# aq_mx_v1-5-0a.net
KiCad netlist of a schematic drawn in EAGLE
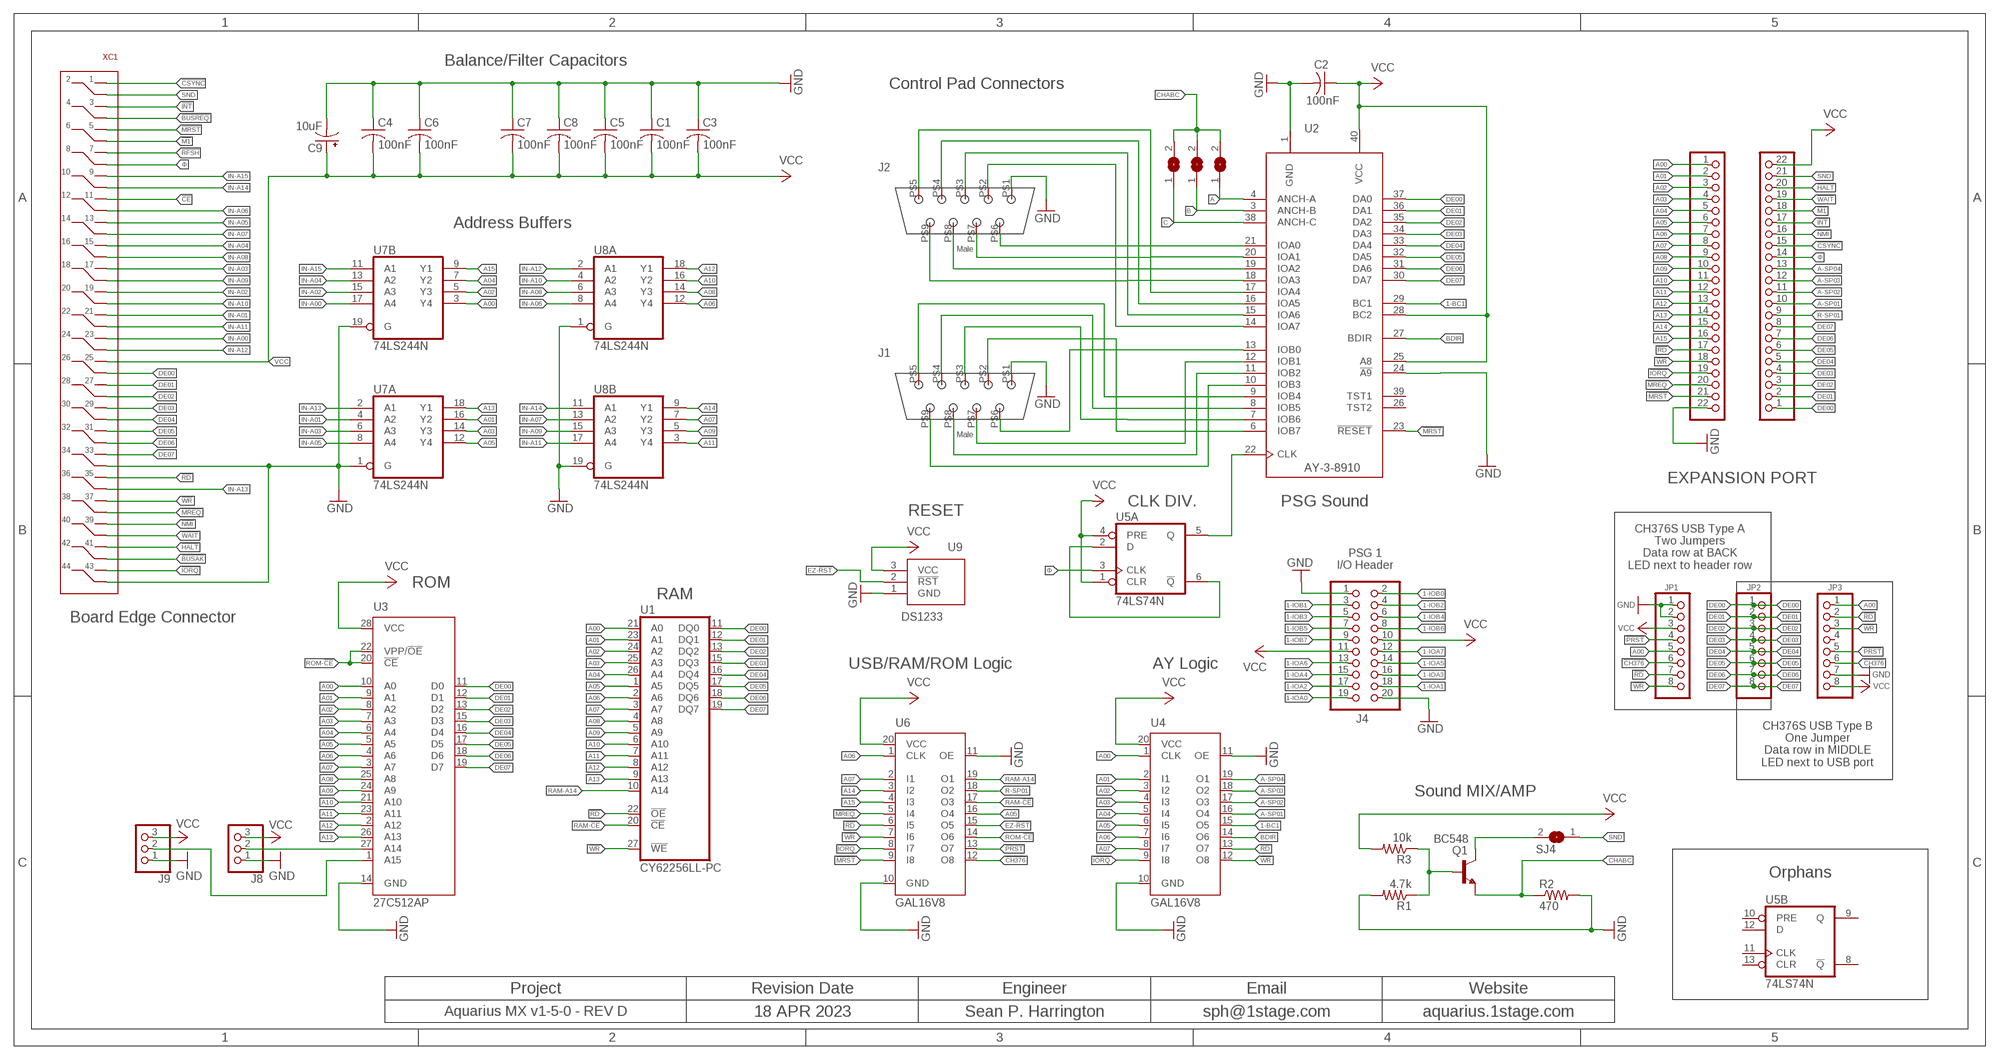
[diagram p0: schematic, sheet 1]

(export (version "E")
  (design (tool "Eeschema 10.0.6"))
  (components
    (comp (ref "C1")
      (value "100nF")
      (footprint "eagle-import:C050-025X075")
      (libsource (lib "eagle-import") (part "C-US050-025X075"))
    )
    (comp (ref "C2")
      (value "100nF")
      (footprint "eagle-import:C050-025X075")
      (libsource (lib "eagle-import") (part "C-US050-025X075"))
    )
    (comp (ref "C3")
      (value "100nF")
      (footprint "eagle-import:C050-025X075")
      (libsource (lib "eagle-import") (part "C-US050-025X075"))
    )
    (comp (ref "C4")
      (value "100nF")
      (footprint "eagle-import:C050-025X075")
      (libsource (lib "eagle-import") (part "C-US050-025X075"))
    )
    (comp (ref "C5")
      (value "100nF")
      (footprint "eagle-import:C050-025X075")
      (libsource (lib "eagle-import") (part "C-US050-025X075"))
    )
    (comp (ref "C6")
      (value "100nF")
      (footprint "eagle-import:C050-025X075")
      (libsource (lib "eagle-import") (part "C-US050-025X075"))
    )
    (comp (ref "C7")
      (value "100nF")
      (footprint "eagle-import:C050-025X075")
      (libsource (lib "eagle-import") (part "C-US050-025X075"))
    )
    (comp (ref "C8")
      (value "100nF")
      (footprint "eagle-import:C050-025X075")
      (libsource (lib "eagle-import") (part "C-US050-025X075"))
    )
    (comp (ref "C9")
      (value "10uF")
      (footprint "eagle-import:E22-6")
      (libsource (lib "eagle-import") (part "CPOL-USE22-6AXIAL"))
    )
    (comp (ref "J1")
      (value "DB9-MALE-RA")
      (footprint "eagle-import:DB9-MALE-RA")
      (libsource (lib "eagle-import") (part "DB9-MALE-RA"))
    )
    (comp (ref "J2")
      (value "DB9-MALE-RA")
      (footprint "eagle-import:DB9-MALE-RA")
      (libsource (lib "eagle-import") (part "DB9-MALE-RA"))
    )
    (comp (ref "J4")
      (value "PINHD-2X10")
      (footprint "eagle-import:2X10")
      (libsource (lib "eagle-import") (part "PINHD-2X10"))
    )
    (comp (ref "J6")
      (value "PINHD-1X22")
      (footprint "eagle-import:1X22")
      (libsource (lib "eagle-import") (part "PINHD-1X22"))
    )
    (comp (ref "J7")
      (value "PINHD-1X22")
      (footprint "eagle-import:1X22")
      (libsource (lib "eagle-import") (part "PINHD-1X22"))
    )
    (comp (ref "J8")
      (value "PINHD-1X3")
      (footprint "eagle-import:1X03")
      (libsource (lib "eagle-import") (part "PINHD-1X3"))
    )
    (comp (ref "J9")
      (value "PINHD-1X3")
      (footprint "eagle-import:1X03")
      (libsource (lib "eagle-import") (part "PINHD-1X3"))
    )
    (comp (ref "JP1")
      (value "PINHD-1X8")
      (footprint "eagle-import:1X08")
      (libsource (lib "eagle-import") (part "PINHD-1X8"))
    )
    (comp (ref "JP2")
      (value "PINHD-1X8")
      (footprint "eagle-import:1X08")
      (libsource (lib "eagle-import") (part "PINHD-1X8"))
    )
    (comp (ref "JP3")
      (value "PINHD-1X8")
      (footprint "eagle-import:1X08")
      (libsource (lib "eagle-import") (part "PINHD-1X8"))
    )
    (comp (ref "Q1")
      (value "BC548")
      (footprint "eagle-import:TO92-CBE")
      (libsource (lib "eagle-import") (part "-NPN-TO92-CBEBC548"))
    )
    (comp (ref "R1")
      (value "4.7k")
      (footprint "eagle-import:0204_7")
      (libsource (lib "eagle-import") (part "R-US_0204/7"))
    )
    (comp (ref "R2")
      (value "470")
      (footprint "eagle-import:0204_7")
      (libsource (lib "eagle-import") (part "R-US_0204/7"))
    )
    (comp (ref "R3")
      (value "10k")
      (footprint "eagle-import:0204_7")
      (libsource (lib "eagle-import") (part "R-US_0204/7"))
    )
    (comp (ref "SJ1") (value "SJ") (footprint "eagle-import:SJ") (libsource (lib "eagle-import") (part "SJ")))
    (comp (ref "SJ2") (value "SJ") (footprint "eagle-import:SJ") (libsource (lib "eagle-import") (part "SJ")))
    (comp (ref "SJ3") (value "SJ") (footprint "eagle-import:SJ") (libsource (lib "eagle-import") (part "SJ")))
    (comp (ref "SJ4") (value "SJ") (footprint "eagle-import:SJ") (libsource (lib "eagle-import") (part "SJ")))
    (comp (ref "U1")
      (value "CY62256LL-PC")
      (footprint "eagle-import:DIL28-6")
      (libsource (lib "eagle-import") (part "CY62256LL-?PC"))
    )
    (comp (ref "U2")
      (value "AY-3-8910")
      (footprint "eagle-import:RAD38910-DIL40-6")
      (libsource (lib "eagle-import") (part "RAD38910DIL40-6"))
    )
    (comp (ref "U3")
      (value "27C512AP")
      (footprint "eagle-import:DIL28-6")
      (fields (field (name "MPN") "M27C512-90B6"))
      (libsource (lib "eagle-import") (part "27512APC"))
    )
    (comp (ref "U4")
      (value "GAL16V8")
      (footprint "eagle-import:DIL20")
      (fields (field (name "MPN") "ATF16V8CZ-15PU"))
      (libsource (lib "eagle-import") (part "ATF16V8BP3"))
    )
    (comp (ref "U5")
      (value "74LS74N")
      (footprint "eagle-import:DIL14")
      (libsource (lib "eagle-import") (part "7474NLS"))
    )
    (comp (ref "U6")
      (value "GAL16V8")
      (footprint "eagle-import:DIL20")
      (fields (field (name "MPN") "ATF16V8CZ-15PU"))
      (libsource (lib "eagle-import") (part "ATF16V8BP3"))
    )
    (comp (ref "U7")
      (value "74LS244N")
      (footprint "eagle-import:DIL20")
      (libsource (lib "eagle-import") (part "74244NLS"))
    )
    (comp (ref "U8")
      (value "74LS244N")
      (footprint "eagle-import:DIL20")
      (libsource (lib "eagle-import") (part "74244NLS"))
    )
    (comp (ref "U9")
      (value "DS1233")
      (footprint "eagle-import:TO-92")
      (fields
        (field (name "ARROW_PART_NUMBER") "DS1233-10+")
        (field (name "MOUSER_PART_NUMBER") "700-DS1233-10")
      )
      (libsource (lib "eagle-import") (part "DS1233-10+"))
    )
    (comp (ref "XC1")
      (value "AQ-CART-EDGE")
      (footprint "eagle-import:AQ-CART-EDGE")
      (libsource (lib "eagle-import") (part "AQ-CART-EDGE"))
    )
  )
  (nets
    (net (code "1") (name "/EZ-~{RST}") (class "Default")
      (node (ref "U6") (pin "15") (pinfunction "O5_15") (pintype "output"))
      (node (ref "U9") (pin "2") (pinfunction "~{RST}_2") (pintype "input"))
    )
    (net (code "2") (name "/RAM-~{CE}") (class "Default")
      (node (ref "U1") (pin "20") (pinfunction "~{CE}_20") (pintype "input"))
      (node (ref "U6") (pin "17") (pinfunction "O3_17") (pintype "output"))
    )
    (net (code "3") (name "/ROM-~{CE}") (class "Default")
      (node (ref "U3") (pin "20") (pinfunction "~{CE}_20") (pintype "input"))
      (node (ref "U3") (pin "22") (pinfunction "VPP/~{OE}_22") (pintype "input"))
      (node (ref "U6") (pin "14") (pinfunction "O6_14") (pintype "output"))
    )
    (net (code "4") (name "/~{BUSAK}") (class "Default")
      (node (ref "XC1") (pin "P$42") (pinfunction "X42_P$42") (pintype "bidirectional"))
    )
    (net (code "5") (name "/~{BUSREQ}") (class "Default")
      (node (ref "XC1") (pin "P$4") (pinfunction "X4_P$4") (pintype "bidirectional"))
    )
    (net (code "6") (name "/~{CE}") (class "Default")
      (node (ref "XC1") (pin "P$11") (pinfunction "X11_P$11") (pintype "bidirectional"))
    )
    (net (code "7") (name "/~{CH376}") (class "Default")
      (node (ref "JP1") (pin "6") (pinfunction "6_6") (pintype "passive"))
      (node (ref "JP3") (pin "6") (pinfunction "6_6") (pintype "passive"))
      (node (ref "U6") (pin "12") (pinfunction "O8_12") (pintype "output"))
    )
    (net (code "8") (name "/~{CSYNC}") (class "Default")
      (node (ref "J6") (pin "15") (pinfunction "15_15") (pintype "passive"))
      (node (ref "XC1") (pin "P$1") (pinfunction "X1_P$1") (pintype "bidirectional"))
    )
    (net (code "9") (name "/~{HALT}") (class "Default")
      (node (ref "J6") (pin "20") (pinfunction "20_20") (pintype "passive"))
      (node (ref "XC1") (pin "P$41") (pinfunction "X41_P$41") (pintype "bidirectional"))
    )
    (net (code "10") (name "/~{INT}") (class "Default")
      (node (ref "J6") (pin "17") (pinfunction "17_17") (pintype "passive"))
      (node (ref "XC1") (pin "P$3") (pinfunction "X3_P$3") (pintype "bidirectional"))
    )
    (net (code "11") (name "/~{IORQ}") (class "Default")
      (node (ref "J7") (pin "19") (pinfunction "19_19") (pintype "passive"))
      (node (ref "U4") (pin "9") (pinfunction "I8_9") (pintype "input"))
      (node (ref "U6") (pin "8") (pinfunction "I7_8") (pintype "input"))
      (node (ref "XC1") (pin "P$43") (pinfunction "X43_P$43") (pintype "bidirectional"))
    )
    (net (code "12") (name "/~{M1}") (class "Default")
      (node (ref "J6") (pin "18") (pinfunction "18_18") (pintype "passive"))
      (node (ref "XC1") (pin "P$6") (pinfunction "X6_P$6") (pintype "bidirectional"))
    )
    (net (code "13") (name "/~{MREQ}") (class "Default")
      (node (ref "J7") (pin "20") (pinfunction "20_20") (pintype "passive"))
      (node (ref "U6") (pin "5") (pinfunction "I4_5") (pintype "input"))
      (node (ref "XC1") (pin "P$38") (pinfunction "X38_P$38") (pintype "bidirectional"))
    )
    (net (code "14") (name "/~{MRST}") (class "Default")
      (node (ref "J7") (pin "21") (pinfunction "21_21") (pintype "passive"))
      (node (ref "U2") (pin "23") (pinfunction "~{RESET}_23") (pintype "bidirectional"))
      (node (ref "U6") (pin "9") (pinfunction "I8_9") (pintype "input"))
      (node (ref "XC1") (pin "P$5") (pinfunction "X5_P$5") (pintype "bidirectional"))
    )
    (net (code "15") (name "/~{NMI}") (class "Default")
      (node (ref "J6") (pin "16") (pinfunction "16_16") (pintype "passive"))
      (node (ref "XC1") (pin "P$39") (pinfunction "X39_P$39") (pintype "bidirectional"))
    )
    (net (code "16") (name "/~{PRST}") (class "Default")
      (node (ref "JP1") (pin "4") (pinfunction "4_4") (pintype "passive"))
      (node (ref "JP3") (pin "5") (pinfunction "5_5") (pintype "passive"))
      (node (ref "U6") (pin "13") (pinfunction "O7_13") (pintype "output"))
    )
    (net (code "17") (name "/~{RD}") (class "Default")
      (node (ref "J7") (pin "17") (pinfunction "17_17") (pintype "passive"))
      (node (ref "JP1") (pin "7") (pinfunction "7_7") (pintype "passive"))
      (node (ref "JP3") (pin "2") (pinfunction "2_2") (pintype "passive"))
      (node (ref "U1") (pin "22") (pinfunction "~{OE}_22") (pintype "input"))
      (node (ref "U4") (pin "13") (pinfunction "O7_13") (pintype "output"))
      (node (ref "U6") (pin "6") (pinfunction "I5_6") (pintype "input"))
      (node (ref "XC1") (pin "P$35") (pinfunction "X35_P$35") (pintype "bidirectional"))
    )
    (net (code "18") (name "/~{RFSH}") (class "Default")
      (node (ref "XC1") (pin "P$7") (pinfunction "X7_P$7") (pintype "bidirectional"))
    )
    (net (code "19") (name "/~{WAIT}") (class "Default")
      (node (ref "J6") (pin "19") (pinfunction "19_19") (pintype "passive"))
      (node (ref "XC1") (pin "P$40") (pinfunction "X40_P$40") (pintype "bidirectional"))
    )
    (net (code "20") (name "/~{WR}") (class "Default")
      (node (ref "J7") (pin "18") (pinfunction "18_18") (pintype "passive"))
      (node (ref "JP1") (pin "8") (pinfunction "8_8") (pintype "passive"))
      (node (ref "JP3") (pin "3") (pinfunction "3_3") (pintype "passive"))
      (node (ref "U1") (pin "27") (pinfunction "~{WE}_27") (pintype "input"))
      (node (ref "U4") (pin "12") (pinfunction "O8_12") (pintype "output"))
      (node (ref "U6") (pin "7") (pinfunction "I6_7") (pintype "input"))
      (node (ref "XC1") (pin "P$37") (pinfunction "X37_P$37") (pintype "bidirectional"))
    )
    (net (code "21") (name "1-BC1") (class "Default")
      (node (ref "U2") (pin "29") (pinfunction "BC1_29") (pintype "bidirectional"))
      (node (ref "U4") (pin "15") (pinfunction "O5_15") (pintype "output"))
    )
    (net (code "22") (name "1-IOA0") (class "Default")
      (node (ref "J2") (pin "P$6") (pinfunction "P$6_P$6") (pintype "bidirectional"))
      (node (ref "J4") (pin "19") (pinfunction "19_19") (pintype "passive"))
      (node (ref "U2") (pin "21") (pinfunction "IOA0_21") (pintype "bidirectional"))
    )
    (net (code "23") (name "1-IOA1") (class "Default")
      (node (ref "J2") (pin "P$7") (pinfunction "P$7_P$7") (pintype "bidirectional"))
      (node (ref "J4") (pin "18") (pinfunction "18_18") (pintype "passive"))
      (node (ref "U2") (pin "20") (pinfunction "IOA1_20") (pintype "bidirectional"))
    )
    (net (code "24") (name "1-IOA2") (class "Default")
      (node (ref "J2") (pin "P$8") (pinfunction "P$8_P$8") (pintype "bidirectional"))
      (node (ref "J4") (pin "17") (pinfunction "17_17") (pintype "passive"))
      (node (ref "U2") (pin "19") (pinfunction "IOA2_19") (pintype "bidirectional"))
    )
    (net (code "25") (name "1-IOA3") (class "Default")
      (node (ref "J2") (pin "P$9") (pinfunction "P$9_P$9") (pintype "bidirectional"))
      (node (ref "J4") (pin "16") (pinfunction "16_16") (pintype "passive"))
      (node (ref "U2") (pin "18") (pinfunction "IOA3_18") (pintype "bidirectional"))
    )
    (net (code "26") (name "1-IOA4") (class "Default")
      (node (ref "J2") (pin "P$5") (pinfunction "P$5_P$5") (pintype "bidirectional"))
      (node (ref "J4") (pin "15") (pinfunction "15_15") (pintype "passive"))
      (node (ref "U2") (pin "17") (pinfunction "IOA4_17") (pintype "bidirectional"))
    )
    (net (code "27") (name "1-IOA5") (class "Default")
      (node (ref "J2") (pin "P$4") (pinfunction "P$4_P$4") (pintype "bidirectional"))
      (node (ref "J4") (pin "14") (pinfunction "14_14") (pintype "passive"))
      (node (ref "U2") (pin "16") (pinfunction "IOA5_16") (pintype "bidirectional"))
    )
    (net (code "28") (name "1-IOA6") (class "Default")
      (node (ref "J2") (pin "P$3") (pinfunction "P$3_P$3") (pintype "bidirectional"))
      (node (ref "J4") (pin "13") (pinfunction "13_13") (pintype "passive"))
      (node (ref "U2") (pin "15") (pinfunction "IOA6_15") (pintype "bidirectional"))
    )
    (net (code "29") (name "1-IOA7") (class "Default")
      (node (ref "J2") (pin "P$2") (pinfunction "P$2_P$2") (pintype "bidirectional"))
      (node (ref "J4") (pin "12") (pinfunction "12_12") (pintype "passive"))
      (node (ref "U2") (pin "14") (pinfunction "IOA7_14") (pintype "bidirectional"))
    )
    (net (code "30") (name "1-IOB0") (class "Default")
      (node (ref "J1") (pin "P$6") (pinfunction "P$6_P$6") (pintype "bidirectional"))
      (node (ref "J4") (pin "2") (pinfunction "2_2") (pintype "passive"))
      (node (ref "U2") (pin "13") (pinfunction "IOB0_13") (pintype "bidirectional"))
    )
    (net (code "31") (name "1-IOB1") (class "Default")
      (node (ref "J1") (pin "P$7") (pinfunction "P$7_P$7") (pintype "bidirectional"))
      (node (ref "J4") (pin "3") (pinfunction "3_3") (pintype "passive"))
      (node (ref "U2") (pin "12") (pinfunction "IOB1_12") (pintype "bidirectional"))
    )
    (net (code "32") (name "1-IOB2") (class "Default")
      (node (ref "J1") (pin "P$8") (pinfunction "P$8_P$8") (pintype "bidirectional"))
      (node (ref "J4") (pin "4") (pinfunction "4_4") (pintype "passive"))
      (node (ref "U2") (pin "11") (pinfunction "IOB2_11") (pintype "bidirectional"))
    )
    (net (code "33") (name "1-IOB3") (class "Default")
      (node (ref "J1") (pin "P$9") (pinfunction "P$9_P$9") (pintype "bidirectional"))
      (node (ref "J4") (pin "5") (pinfunction "5_5") (pintype "passive"))
      (node (ref "U2") (pin "10") (pinfunction "IOB3_10") (pintype "bidirectional"))
    )
    (net (code "34") (name "1-IOB4") (class "Default")
      (node (ref "J1") (pin "P$5") (pinfunction "P$5_P$5") (pintype "bidirectional"))
      (node (ref "J4") (pin "6") (pinfunction "6_6") (pintype "passive"))
      (node (ref "U2") (pin "9") (pinfunction "IOB4_9") (pintype "bidirectional"))
    )
    (net (code "35") (name "1-IOB5") (class "Default")
      (node (ref "J1") (pin "P$4") (pinfunction "P$4_P$4") (pintype "bidirectional"))
      (node (ref "J4") (pin "7") (pinfunction "7_7") (pintype "passive"))
      (node (ref "U2") (pin "8") (pinfunction "IOB5_8") (pintype "bidirectional"))
    )
    (net (code "36") (name "1-IOB6") (class "Default")
      (node (ref "J1") (pin "P$3") (pinfunction "P$3_P$3") (pintype "bidirectional"))
      (node (ref "J4") (pin "8") (pinfunction "8_8") (pintype "passive"))
      (node (ref "U2") (pin "7") (pinfunction "IOB6_7") (pintype "bidirectional"))
    )
    (net (code "37") (name "1-IOB7") (class "Default")
      (node (ref "J1") (pin "P$2") (pinfunction "P$2_P$2") (pintype "bidirectional"))
      (node (ref "J4") (pin "9") (pinfunction "9_9") (pintype "passive"))
      (node (ref "U2") (pin "6") (pinfunction "IOB7_6") (pintype "bidirectional"))
    )
    (net (code "38") (name "A") (class "Default")
      (node (ref "SJ1") (pin "1") (pinfunction "1_1") (pintype "passive"))
      (node (ref "U2") (pin "4") (pinfunction "ANCH-A_4") (pintype "bidirectional"))
    )
    (net (code "39") (name "A-SP01") (class "Default")
      (node (ref "J6") (pin "10") (pinfunction "10_10") (pintype "passive"))
      (node (ref "U4") (pin "16") (pinfunction "O4_16") (pintype "output"))
    )
    (net (code "40") (name "A-SP02") (class "Default")
      (node (ref "J6") (pin "11") (pinfunction "11_11") (pintype "passive"))
      (node (ref "U4") (pin "17") (pinfunction "O3_17") (pintype "output"))
    )
    (net (code "41") (name "A-SP03") (class "Default")
      (node (ref "J6") (pin "12") (pinfunction "12_12") (pintype "passive"))
      (node (ref "U4") (pin "18") (pinfunction "O2_18") (pintype "output"))
    )
    (net (code "42") (name "A-SP04") (class "Default")
      (node (ref "J6") (pin "13") (pinfunction "13_13") (pintype "passive"))
      (node (ref "U4") (pin "19") (pinfunction "O1_19") (pintype "output"))
    )
    (net (code "43") (name "A00") (class "Default")
      (node (ref "J7") (pin "1") (pinfunction "1_1") (pintype "passive"))
      (node (ref "JP1") (pin "5") (pinfunction "5_5") (pintype "passive"))
      (node (ref "JP3") (pin "1") (pinfunction "1_1") (pintype "passive"))
      (node (ref "U1") (pin "21") (pinfunction "A0_21") (pintype "input"))
      (node (ref "U3") (pin "10") (pinfunction "A0_10") (pintype "input"))
      (node (ref "U4") (pin "1") (pinfunction "CLK_1") (pintype "input"))
      (node (ref "U7") (pin "3") (pinfunction "Y4_3") (pintype "tri_state"))
    )
    (net (code "44") (name "A01") (class "Default")
      (node (ref "J7") (pin "2") (pinfunction "2_2") (pintype "passive"))
      (node (ref "U1") (pin "23") (pinfunction "A1_23") (pintype "input"))
      (node (ref "U3") (pin "9") (pinfunction "A1_9") (pintype "input"))
      (node (ref "U4") (pin "2") (pinfunction "I1_2") (pintype "input"))
      (node (ref "U7") (pin "16") (pinfunction "Y2_16") (pintype "tri_state"))
    )
    (net (code "45") (name "A02") (class "Default")
      (node (ref "J7") (pin "3") (pinfunction "3_3") (pintype "passive"))
      (node (ref "U1") (pin "24") (pinfunction "A2_24") (pintype "input"))
      (node (ref "U3") (pin "8") (pinfunction "A2_8") (pintype "input"))
      (node (ref "U4") (pin "3") (pinfunction "I2_3") (pintype "input"))
      (node (ref "U7") (pin "5") (pinfunction "Y3_5") (pintype "tri_state"))
    )
    (net (code "46") (name "A03") (class "Default")
      (node (ref "J7") (pin "4") (pinfunction "4_4") (pintype "passive"))
      (node (ref "U1") (pin "25") (pinfunction "A3_25") (pintype "input"))
      (node (ref "U3") (pin "7") (pinfunction "A3_7") (pintype "input"))
      (node (ref "U4") (pin "4") (pinfunction "I3_4") (pintype "input"))
      (node (ref "U7") (pin "14") (pinfunction "Y3_14") (pintype "tri_state"))
    )
    (net (code "47") (name "A04") (class "Default")
      (node (ref "J7") (pin "5") (pinfunction "5_5") (pintype "passive"))
      (node (ref "U1") (pin "26") (pinfunction "A4_26") (pintype "input"))
      (node (ref "U3") (pin "6") (pinfunction "A4_6") (pintype "input"))
      (node (ref "U4") (pin "5") (pinfunction "I4_5") (pintype "input"))
      (node (ref "U7") (pin "7") (pinfunction "Y2_7") (pintype "tri_state"))
    )
    (net (code "48") (name "A05") (class "Default")
      (node (ref "J7") (pin "6") (pinfunction "6_6") (pintype "passive"))
      (node (ref "U1") (pin "1") (pinfunction "A5_1") (pintype "input"))
      (node (ref "U3") (pin "5") (pinfunction "A5_5") (pintype "input"))
      (node (ref "U4") (pin "6") (pinfunction "I5_6") (pintype "input"))
      (node (ref "U6") (pin "16") (pinfunction "O4_16") (pintype "output"))
      (node (ref "U7") (pin "12") (pinfunction "Y4_12") (pintype "tri_state"))
    )
    (net (code "49") (name "A06") (class "Default")
      (node (ref "J7") (pin "7") (pinfunction "7_7") (pintype "passive"))
      (node (ref "U1") (pin "2") (pinfunction "A6_2") (pintype "input"))
      (node (ref "U3") (pin "4") (pinfunction "A6_4") (pintype "input"))
      (node (ref "U4") (pin "7") (pinfunction "I6_7") (pintype "input"))
      (node (ref "U6") (pin "1") (pinfunction "CLK_1") (pintype "input"))
      (node (ref "U8") (pin "12") (pinfunction "Y4_12") (pintype "tri_state"))
    )
    (net (code "50") (name "A07") (class "Default")
      (node (ref "J7") (pin "8") (pinfunction "8_8") (pintype "passive"))
      (node (ref "U1") (pin "3") (pinfunction "A7_3") (pintype "input"))
      (node (ref "U3") (pin "3") (pinfunction "A7_3") (pintype "input"))
      (node (ref "U4") (pin "8") (pinfunction "I7_8") (pintype "input"))
      (node (ref "U6") (pin "2") (pinfunction "I1_2") (pintype "input"))
      (node (ref "U8") (pin "7") (pinfunction "Y2_7") (pintype "tri_state"))
    )
    (net (code "51") (name "A08") (class "Default")
      (node (ref "J7") (pin "9") (pinfunction "9_9") (pintype "passive"))
      (node (ref "U1") (pin "4") (pinfunction "A8_4") (pintype "input"))
      (node (ref "U3") (pin "25") (pinfunction "A8_25") (pintype "input"))
      (node (ref "U8") (pin "14") (pinfunction "Y3_14") (pintype "tri_state"))
    )
    (net (code "52") (name "A09") (class "Default")
      (node (ref "J7") (pin "10") (pinfunction "10_10") (pintype "passive"))
      (node (ref "U1") (pin "5") (pinfunction "A9_5") (pintype "input"))
      (node (ref "U3") (pin "24") (pinfunction "A9_24") (pintype "input"))
      (node (ref "U8") (pin "5") (pinfunction "Y3_5") (pintype "tri_state"))
    )
    (net (code "53") (name "A10") (class "Default")
      (node (ref "J7") (pin "11") (pinfunction "11_11") (pintype "passive"))
      (node (ref "U1") (pin "6") (pinfunction "A10_6") (pintype "input"))
      (node (ref "U3") (pin "21") (pinfunction "A10_21") (pintype "input"))
      (node (ref "U8") (pin "16") (pinfunction "Y2_16") (pintype "tri_state"))
    )
    (net (code "54") (name "A11") (class "Default")
      (node (ref "J7") (pin "12") (pinfunction "12_12") (pintype "passive"))
      (node (ref "U1") (pin "7") (pinfunction "A11_7") (pintype "input"))
      (node (ref "U3") (pin "23") (pinfunction "A11_23") (pintype "input"))
      (node (ref "U8") (pin "3") (pinfunction "Y4_3") (pintype "tri_state"))
    )
    (net (code "55") (name "A12") (class "Default")
      (node (ref "J7") (pin "13") (pinfunction "13_13") (pintype "passive"))
      (node (ref "U1") (pin "8") (pinfunction "A12_8") (pintype "input"))
      (node (ref "U3") (pin "2") (pinfunction "A12_2") (pintype "input"))
      (node (ref "U8") (pin "18") (pinfunction "Y1_18") (pintype "tri_state"))
    )
    (net (code "56") (name "A13") (class "Default")
      (node (ref "J7") (pin "14") (pinfunction "14_14") (pintype "passive"))
      (node (ref "U1") (pin "9") (pinfunction "A13_9") (pintype "input"))
      (node (ref "U3") (pin "26") (pinfunction "A13_26") (pintype "input"))
      (node (ref "U7") (pin "18") (pinfunction "Y1_18") (pintype "tri_state"))
    )
    (net (code "57") (name "A14") (class "Default")
      (node (ref "J7") (pin "15") (pinfunction "15_15") (pintype "passive"))
      (node (ref "U6") (pin "3") (pinfunction "I2_3") (pintype "input"))
      (node (ref "U8") (pin "9") (pinfunction "Y1_9") (pintype "tri_state"))
    )
    (net (code "58") (name "A15") (class "Default")
      (node (ref "J7") (pin "16") (pinfunction "16_16") (pintype "passive"))
      (node (ref "U6") (pin "4") (pinfunction "I3_4") (pintype "input"))
      (node (ref "U7") (pin "9") (pinfunction "Y1_9") (pintype "tri_state"))
    )
    (net (code "59") (name "B") (class "Default")
      (node (ref "SJ2") (pin "1") (pinfunction "1_1") (pintype "passive"))
      (node (ref "U2") (pin "3") (pinfunction "ANCH-B_3") (pintype "bidirectional"))
    )
    (net (code "60") (name "BDIR") (class "Default")
      (node (ref "U2") (pin "27") (pinfunction "BDIR_27") (pintype "bidirectional"))
      (node (ref "U4") (pin "14") (pinfunction "O6_14") (pintype "output"))
    )
    (net (code "61") (name "C") (class "Default")
      (node (ref "SJ3") (pin "1") (pinfunction "1_1") (pintype "passive"))
      (node (ref "U2") (pin "38") (pinfunction "ANCH-C_38") (pintype "bidirectional"))
    )
    (net (code "62") (name "CHABC") (class "Default")
      (node (ref "Q1") (pin "E") (pinfunction "E_E") (pintype "passive"))
      (node (ref "R2") (pin "1") (pinfunction "1_1") (pintype "passive"))
      (node (ref "SJ1") (pin "2") (pinfunction "2_2") (pintype "passive"))
      (node (ref "SJ2") (pin "2") (pinfunction "2_2") (pintype "passive"))
      (node (ref "SJ3") (pin "2") (pinfunction "2_2") (pintype "passive"))
    )
    (net (code "63") (name "DE00") (class "Default")
      (node (ref "J6") (pin "1") (pinfunction "1_1") (pintype "passive"))
      (node (ref "JP2") (pin "1") (pinfunction "1_1") (pintype "passive"))
      (node (ref "U1") (pin "11") (pinfunction "DQ0_11") (pintype "bidirectional"))
      (node (ref "U2") (pin "37") (pinfunction "DA0_37") (pintype "bidirectional"))
      (node (ref "U3") (pin "11") (pinfunction "D0_11") (pintype "tri_state"))
      (node (ref "XC1") (pin "P$26") (pinfunction "X26_P$26") (pintype "bidirectional"))
    )
    (net (code "64") (name "DE01") (class "Default")
      (node (ref "J6") (pin "2") (pinfunction "2_2") (pintype "passive"))
      (node (ref "JP2") (pin "2") (pinfunction "2_2") (pintype "passive"))
      (node (ref "U1") (pin "12") (pinfunction "DQ1_12") (pintype "bidirectional"))
      (node (ref "U2") (pin "36") (pinfunction "DA1_36") (pintype "bidirectional"))
      (node (ref "U3") (pin "12") (pinfunction "D1_12") (pintype "tri_state"))
      (node (ref "XC1") (pin "P$27") (pinfunction "X27_P$27") (pintype "bidirectional"))
    )
    (net (code "65") (name "DE02") (class "Default")
      (node (ref "J6") (pin "3") (pinfunction "3_3") (pintype "passive"))
      (node (ref "JP2") (pin "3") (pinfunction "3_3") (pintype "passive"))
      (node (ref "U1") (pin "13") (pinfunction "DQ2_13") (pintype "bidirectional"))
      (node (ref "U2") (pin "35") (pinfunction "DA2_35") (pintype "bidirectional"))
      (node (ref "U3") (pin "13") (pinfunction "D2_13") (pintype "tri_state"))
      (node (ref "XC1") (pin "P$28") (pinfunction "X28_P$28") (pintype "bidirectional"))
    )
    (net (code "66") (name "DE03") (class "Default")
      (node (ref "J6") (pin "4") (pinfunction "4_4") (pintype "passive"))
      (node (ref "JP2") (pin "4") (pinfunction "4_4") (pintype "passive"))
      (node (ref "U1") (pin "15") (pinfunction "DQ3_15") (pintype "bidirectional"))
      (node (ref "U2") (pin "34") (pinfunction "DA3_34") (pintype "bidirectional"))
      (node (ref "U3") (pin "15") (pinfunction "D3_15") (pintype "tri_state"))
      (node (ref "XC1") (pin "P$29") (pinfunction "X29_P$29") (pintype "bidirectional"))
    )
    (net (code "67") (name "DE04") (class "Default")
      (node (ref "J6") (pin "5") (pinfunction "5_5") (pintype "passive"))
      (node (ref "JP2") (pin "5") (pinfunction "5_5") (pintype "passive"))
      (node (ref "U1") (pin "16") (pinfunction "DQ4_16") (pintype "bidirectional"))
      (node (ref "U2") (pin "33") (pinfunction "DA4_33") (pintype "bidirectional"))
      (node (ref "U3") (pin "16") (pinfunction "D4_16") (pintype "tri_state"))
      (node (ref "XC1") (pin "P$30") (pinfunction "X30_P$30") (pintype "bidirectional"))
    )
    (net (code "68") (name "DE05") (class "Default")
      (node (ref "J6") (pin "6") (pinfunction "6_6") (pintype "passive"))
      (node (ref "JP2") (pin "6") (pinfunction "6_6") (pintype "passive"))
      (node (ref "U1") (pin "17") (pinfunction "DQ5_17") (pintype "bidirectional"))
      (node (ref "U2") (pin "32") (pinfunction "DA5_32") (pintype "bidirectional"))
      (node (ref "U3") (pin "17") (pinfunction "D5_17") (pintype "tri_state"))
      (node (ref "XC1") (pin "P$31") (pinfunction "X31_P$31") (pintype "bidirectional"))
    )
    (net (code "69") (name "DE06") (class "Default")
      (node (ref "J6") (pin "7") (pinfunction "7_7") (pintype "passive"))
      (node (ref "JP2") (pin "7") (pinfunction "7_7") (pintype "passive"))
      (node (ref "U1") (pin "18") (pinfunction "DQ6_18") (pintype "bidirectional"))
      (node (ref "U2") (pin "31") (pinfunction "DA6_31") (pintype "bidirectional"))
      (node (ref "U3") (pin "18") (pinfunction "D6_18") (pintype "tri_state"))
      (node (ref "XC1") (pin "P$32") (pinfunction "X32_P$32") (pintype "bidirectional"))
    )
    (net (code "70") (name "DE07") (class "Default")
      (node (ref "J6") (pin "8") (pinfunction "8_8") (pintype "passive"))
      (node (ref "JP2") (pin "8") (pinfunction "8_8") (pintype "passive"))
      (node (ref "U1") (pin "19") (pinfunction "DQ7_19") (pintype "bidirectional"))
      (node (ref "U2") (pin "30") (pinfunction "DA7_30") (pintype "bidirectional"))
      (node (ref "U3") (pin "19") (pinfunction "D7_19") (pintype "tri_state"))
      (node (ref "XC1") (pin "P$33") (pinfunction "X33_P$33") (pintype "bidirectional"))
    )
    (net (code "71") (name "GND") (class "Default")
      (node (ref "C1") (pin "1") (pinfunction "1_1") (pintype "passive"))
      (node (ref "C2") (pin "2") (pinfunction "2_2") (pintype "passive"))
      (node (ref "C3") (pin "1") (pinfunction "1_1") (pintype "passive"))
      (node (ref "C4") (pin "1") (pinfunction "1_1") (pintype "passive"))
      (node (ref "C5") (pin "1") (pinfunction "1_1") (pintype "passive"))
      (node (ref "C6") (pin "1") (pinfunction "1_1") (pintype "passive"))
      (node (ref "C7") (pin "1") (pinfunction "1_1") (pintype "passive"))
      (node (ref "C8") (pin "1") (pinfunction "1_1") (pintype "passive"))
      (node (ref "C9") (pin "-") (pinfunction "-_-") (pintype "passive"))
      (node (ref "J1") (pin "P$1") (pinfunction "P$1_P$1") (pintype "bidirectional"))
      (node (ref "J2") (pin "P$1") (pinfunction "P$1_P$1") (pintype "bidirectional"))
      (node (ref "J4") (pin "1") (pinfunction "1_1") (pintype "passive"))
      (node (ref "J4") (pin "20") (pinfunction "20_20") (pintype "passive"))
      (node (ref "J7") (pin "22") (pinfunction "22_22") (pintype "passive"))
      (node (ref "J8") (pin "1") (pinfunction "1_1") (pintype "passive"))
      (node (ref "J9") (pin "1") (pinfunction "1_1") (pintype "passive"))
      (node (ref "JP1") (pin "1") (pinfunction "1_1") (pintype "passive"))
      (node (ref "JP1") (pin "2") (pinfunction "2_2") (pintype "passive"))
      (node (ref "JP3") (pin "7") (pinfunction "7_7") (pintype "passive"))
      (node (ref "R1") (pin "2") (pinfunction "2_2") (pintype "passive"))
      (node (ref "R2") (pin "2") (pinfunction "2_2") (pintype "passive"))
      (node (ref "U2") (pin "1") (pinfunction "GND_1") (pintype "power_in"))
      (node (ref "U2") (pin "24") (pinfunction "~{A9}_24") (pintype "bidirectional"))
      (node (ref "U3") (pin "14") (pinfunction "GND_14") (pintype "power_in"))
      (node (ref "U4") (pin "10") (pinfunction "GND_10") (pintype "power_in"))
      (node (ref "U4") (pin "11") (pinfunction "OE_11") (pintype "input"))
      (node (ref "U6") (pin "10") (pinfunction "GND_10") (pintype "power_in"))
      (node (ref "U6") (pin "11") (pinfunction "OE_11") (pintype "input"))
      (node (ref "U7") (pin "1") (pinfunction "G_1") (pintype "input"))
      (node (ref "U7") (pin "19") (pinfunction "G_19") (pintype "input"))
      (node (ref "U8") (pin "1") (pinfunction "G_1") (pintype "input"))
      (node (ref "U8") (pin "19") (pinfunction "G_19") (pintype "input"))
      (node (ref "U9") (pin "1") (pinfunction "GND_1") (pintype "power_in"))
      (node (ref "XC1") (pin "P$34") (pinfunction "X34_P$34") (pintype "bidirectional"))
      (node (ref "XC1") (pin "P$44") (pinfunction "X44_P$44") (pintype "bidirectional"))
    )
    (net (code "72") (name "IN-A00") (class "Default")
      (node (ref "U7") (pin "17") (pinfunction "A4_17") (pintype "input"))
      (node (ref "XC1") (pin "P$23") (pinfunction "X23_P$23") (pintype "bidirectional"))
    )
    (net (code "73") (name "IN-A01") (class "Default")
      (node (ref "U7") (pin "4") (pinfunction "A2_4") (pintype "input"))
      (node (ref "XC1") (pin "P$21") (pinfunction "X21_P$21") (pintype "bidirectional"))
    )
    (net (code "74") (name "IN-A02") (class "Default")
      (node (ref "U7") (pin "15") (pinfunction "A3_15") (pintype "input"))
      (node (ref "XC1") (pin "P$19") (pinfunction "X19_P$19") (pintype "bidirectional"))
    )
    (net (code "75") (name "IN-A03") (class "Default")
      (node (ref "U7") (pin "6") (pinfunction "A3_6") (pintype "input"))
      (node (ref "XC1") (pin "P$17") (pinfunction "X17_P$17") (pintype "bidirectional"))
    )
    (net (code "76") (name "IN-A04") (class "Default")
      (node (ref "U7") (pin "13") (pinfunction "A2_13") (pintype "input"))
      (node (ref "XC1") (pin "P$15") (pinfunction "X15_P$15") (pintype "bidirectional"))
    )
    (net (code "77") (name "IN-A05") (class "Default")
      (node (ref "U7") (pin "8") (pinfunction "A4_8") (pintype "input"))
      (node (ref "XC1") (pin "P$13") (pinfunction "X13_P$13") (pintype "bidirectional"))
    )
    (net (code "78") (name "IN-A06") (class "Default")
      (node (ref "U8") (pin "8") (pinfunction "A4_8") (pintype "input"))
      (node (ref "XC1") (pin "P$12") (pinfunction "X12_P$12") (pintype "bidirectional"))
    )
    (net (code "79") (name "IN-A07") (class "Default")
      (node (ref "U8") (pin "13") (pinfunction "A2_13") (pintype "input"))
      (node (ref "XC1") (pin "P$14") (pinfunction "X14_P$14") (pintype "bidirectional"))
    )
    (net (code "80") (name "IN-A08") (class "Default")
      (node (ref "U8") (pin "6") (pinfunction "A3_6") (pintype "input"))
      (node (ref "XC1") (pin "P$16") (pinfunction "X16_P$16") (pintype "bidirectional"))
    )
    (net (code "81") (name "IN-A09") (class "Default")
      (node (ref "U8") (pin "15") (pinfunction "A3_15") (pintype "input"))
      (node (ref "XC1") (pin "P$18") (pinfunction "X18_P$18") (pintype "bidirectional"))
    )
    (net (code "82") (name "IN-A10") (class "Default")
      (node (ref "U8") (pin "4") (pinfunction "A2_4") (pintype "input"))
      (node (ref "XC1") (pin "P$20") (pinfunction "X20_P$20") (pintype "bidirectional"))
    )
    (net (code "83") (name "IN-A11") (class "Default")
      (node (ref "U8") (pin "17") (pinfunction "A4_17") (pintype "input"))
      (node (ref "XC1") (pin "P$22") (pinfunction "X22_P$22") (pintype "bidirectional"))
    )
    (net (code "84") (name "IN-A12") (class "Default")
      (node (ref "U8") (pin "2") (pinfunction "A1_2") (pintype "input"))
      (node (ref "XC1") (pin "P$24") (pinfunction "X24_P$24") (pintype "bidirectional"))
    )
    (net (code "85") (name "IN-A13") (class "Default")
      (node (ref "U7") (pin "2") (pinfunction "A1_2") (pintype "input"))
      (node (ref "XC1") (pin "P$36") (pinfunction "X36_P$36") (pintype "bidirectional"))
    )
    (net (code "86") (name "IN-A14") (class "Default")
      (node (ref "U8") (pin "11") (pinfunction "A1_11") (pintype "input"))
      (node (ref "XC1") (pin "P$10") (pinfunction "X10_P$10") (pintype "bidirectional"))
    )
    (net (code "87") (name "IN-A15") (class "Default")
      (node (ref "U7") (pin "11") (pinfunction "A1_11") (pintype "input"))
      (node (ref "XC1") (pin "P$9") (pinfunction "X9_P$9") (pintype "bidirectional"))
    )
    (net (code "88") (name "Net-(Q1-PadB)") (class "Default")
      (node (ref "Q1") (pin "B") (pinfunction "B_B") (pintype "passive"))
      (node (ref "R1") (pin "1") (pinfunction "1_1") (pintype "passive"))
      (node (ref "R3") (pin "1") (pinfunction "1_1") (pintype "passive"))
    )
    (net (code "89") (name "Net-(Q1-PadC)") (class "Default")
      (node (ref "Q1") (pin "C") (pinfunction "C_C") (pintype "passive"))
      (node (ref "SJ4") (pin "2") (pinfunction "2_2") (pintype "passive"))
    )
    (net (code "90") (name "Net-(U2-CLK)") (class "Default")
      (node (ref "U2") (pin "22") (pinfunction "CLK_22") (pintype "input"))
      (node (ref "U5") (pin "5") (pinfunction "Q_5") (pintype "output"))
    )
    (net (code "91") (name "Net-(U3-A14)") (class "Default")
      (node (ref "J8") (pin "2") (pinfunction "2_2") (pintype "passive"))
      (node (ref "U3") (pin "27") (pinfunction "A14_27") (pintype "input"))
    )
    (net (code "92") (name "Net-(U3-A15)") (class "Default")
      (node (ref "J9") (pin "2") (pinfunction "2_2") (pintype "passive"))
      (node (ref "U3") (pin "1") (pinfunction "A15_1") (pintype "input"))
    )
    (net (code "93") (name "Net-(U5A-D)") (class "Default")
      (node (ref "U5") (pin "2") (pinfunction "D_2") (pintype "input"))
      (node (ref "U5") (pin "6") (pinfunction "~{Q}_6") (pintype "output"))
    )
    (net (code "94") (name "R-SP01") (class "Default")
      (node (ref "J6") (pin "9") (pinfunction "9_9") (pintype "passive"))
      (node (ref "U6") (pin "18") (pinfunction "O2_18") (pintype "output"))
    )
    (net (code "95") (name "RAM-A14") (class "Default")
      (node (ref "U1") (pin "10") (pinfunction "A14_10") (pintype "input"))
      (node (ref "U6") (pin "19") (pinfunction "O1_19") (pintype "output"))
    )
    (net (code "96") (name "SND") (class "Default")
      (node (ref "J6") (pin "21") (pinfunction "21_21") (pintype "passive"))
      (node (ref "SJ4") (pin "1") (pinfunction "1_1") (pintype "passive"))
      (node (ref "XC1") (pin "P$2") (pinfunction "X2_P$2") (pintype "bidirectional"))
    )
    (net (code "97") (name "VCC") (class "Default")
      (node (ref "C1") (pin "2") (pinfunction "2_2") (pintype "passive"))
      (node (ref "C2") (pin "1") (pinfunction "1_1") (pintype "passive"))
      (node (ref "C3") (pin "2") (pinfunction "2_2") (pintype "passive"))
      (node (ref "C4") (pin "2") (pinfunction "2_2") (pintype "passive"))
      (node (ref "C5") (pin "2") (pinfunction "2_2") (pintype "passive"))
      (node (ref "C6") (pin "2") (pinfunction "2_2") (pintype "passive"))
      (node (ref "C7") (pin "2") (pinfunction "2_2") (pintype "passive"))
      (node (ref "C8") (pin "2") (pinfunction "2_2") (pintype "passive"))
      (node (ref "C9") (pin "+") (pinfunction "+_+") (pintype "passive"))
      (node (ref "J4") (pin "10") (pinfunction "10_10") (pintype "passive"))
      (node (ref "J4") (pin "11") (pinfunction "11_11") (pintype "passive"))
      (node (ref "J6") (pin "22") (pinfunction "22_22") (pintype "passive"))
      (node (ref "J8") (pin "3") (pinfunction "3_3") (pintype "passive"))
      (node (ref "J9") (pin "3") (pinfunction "3_3") (pintype "passive"))
      (node (ref "JP1") (pin "3") (pinfunction "3_3") (pintype "passive"))
      (node (ref "JP3") (pin "8") (pinfunction "8_8") (pintype "passive"))
      (node (ref "R3") (pin "2") (pinfunction "2_2") (pintype "passive"))
      (node (ref "U2") (pin "25") (pinfunction "A8_25") (pintype "bidirectional"))
      (node (ref "U2") (pin "28") (pinfunction "BC2_28") (pintype "bidirectional"))
      (node (ref "U2") (pin "40") (pinfunction "VCC_40") (pintype "power_in"))
      (node (ref "U3") (pin "28") (pinfunction "VCC_28") (pintype "power_in"))
      (node (ref "U4") (pin "20") (pinfunction "VCC_20") (pintype "power_in"))
      (node (ref "U5") (pin "1") (pinfunction "CLR_1") (pintype "input"))
      (node (ref "U5") (pin "4") (pinfunction "PRE_4") (pintype "input"))
      (node (ref "U6") (pin "20") (pinfunction "VCC_20") (pintype "power_in"))
      (node (ref "U9") (pin "3") (pinfunction "VCC_3") (pintype "power_in"))
      (node (ref "XC1") (pin "P$25") (pinfunction "X25_P$25") (pintype "bidirectional"))
    )
    (net (code "98") (name "unconnected-(JP3-Pad4)") (class "Default")
      (node (ref "JP3") (pin "4") (pinfunction "4_4") (pintype "passive"))
    )
    (net (code "99") (name "unconnected-(U2-TST1-Pad39)") (class "Default")
      (node (ref "U2") (pin "39") (pinfunction "TST1_39") (pintype "bidirectional"))
    )
    (net (code "100") (name "unconnected-(U2-TST2-Pad26)") (class "Default")
      (node (ref "U2") (pin "26") (pinfunction "TST2_26") (pintype "bidirectional"))
    )
    (net (code "101") (name "unconnected-(U5B-CLK-Pad11)") (class "Default")
      (node (ref "U5") (pin "11") (pinfunction "CLK_11") (pintype "input"))
    )
    (net (code "102") (name "unconnected-(U5B-CLR-Pad13)") (class "Default")
      (node (ref "U5") (pin "13") (pinfunction "CLR_13") (pintype "input"))
    )
    (net (code "103") (name "unconnected-(U5B-D-Pad12)") (class "Default")
      (node (ref "U5") (pin "12") (pinfunction "D_12") (pintype "input"))
    )
    (net (code "104") (name "unconnected-(U5B-PRE-Pad10)") (class "Default")
      (node (ref "U5") (pin "10") (pinfunction "PRE_10") (pintype "input"))
    )
    (net (code "105") (name "unconnected-(U5B-Q-Pad9)") (class "Default")
      (node (ref "U5") (pin "9") (pinfunction "Q_9") (pintype "output"))
    )
    (net (code "106") (name "unconnected-(U5B-~{Q}-Pad8)") (class "Default")
      (node (ref "U5") (pin "8") (pinfunction "~{Q}_8") (pintype "output"))
    )
    (net (code "107") (name "Φ") (class "Default")
      (node (ref "J6") (pin "14") (pinfunction "14_14") (pintype "passive"))
      (node (ref "U5") (pin "3") (pinfunction "CLK_3") (pintype "input"))
      (node (ref "XC1") (pin "P$8") (pinfunction "X8_P$8") (pintype "bidirectional"))
    )
  )
)
